# OpenScoreboard.net
KiCad netlist of a schematic drawn in EAGLE
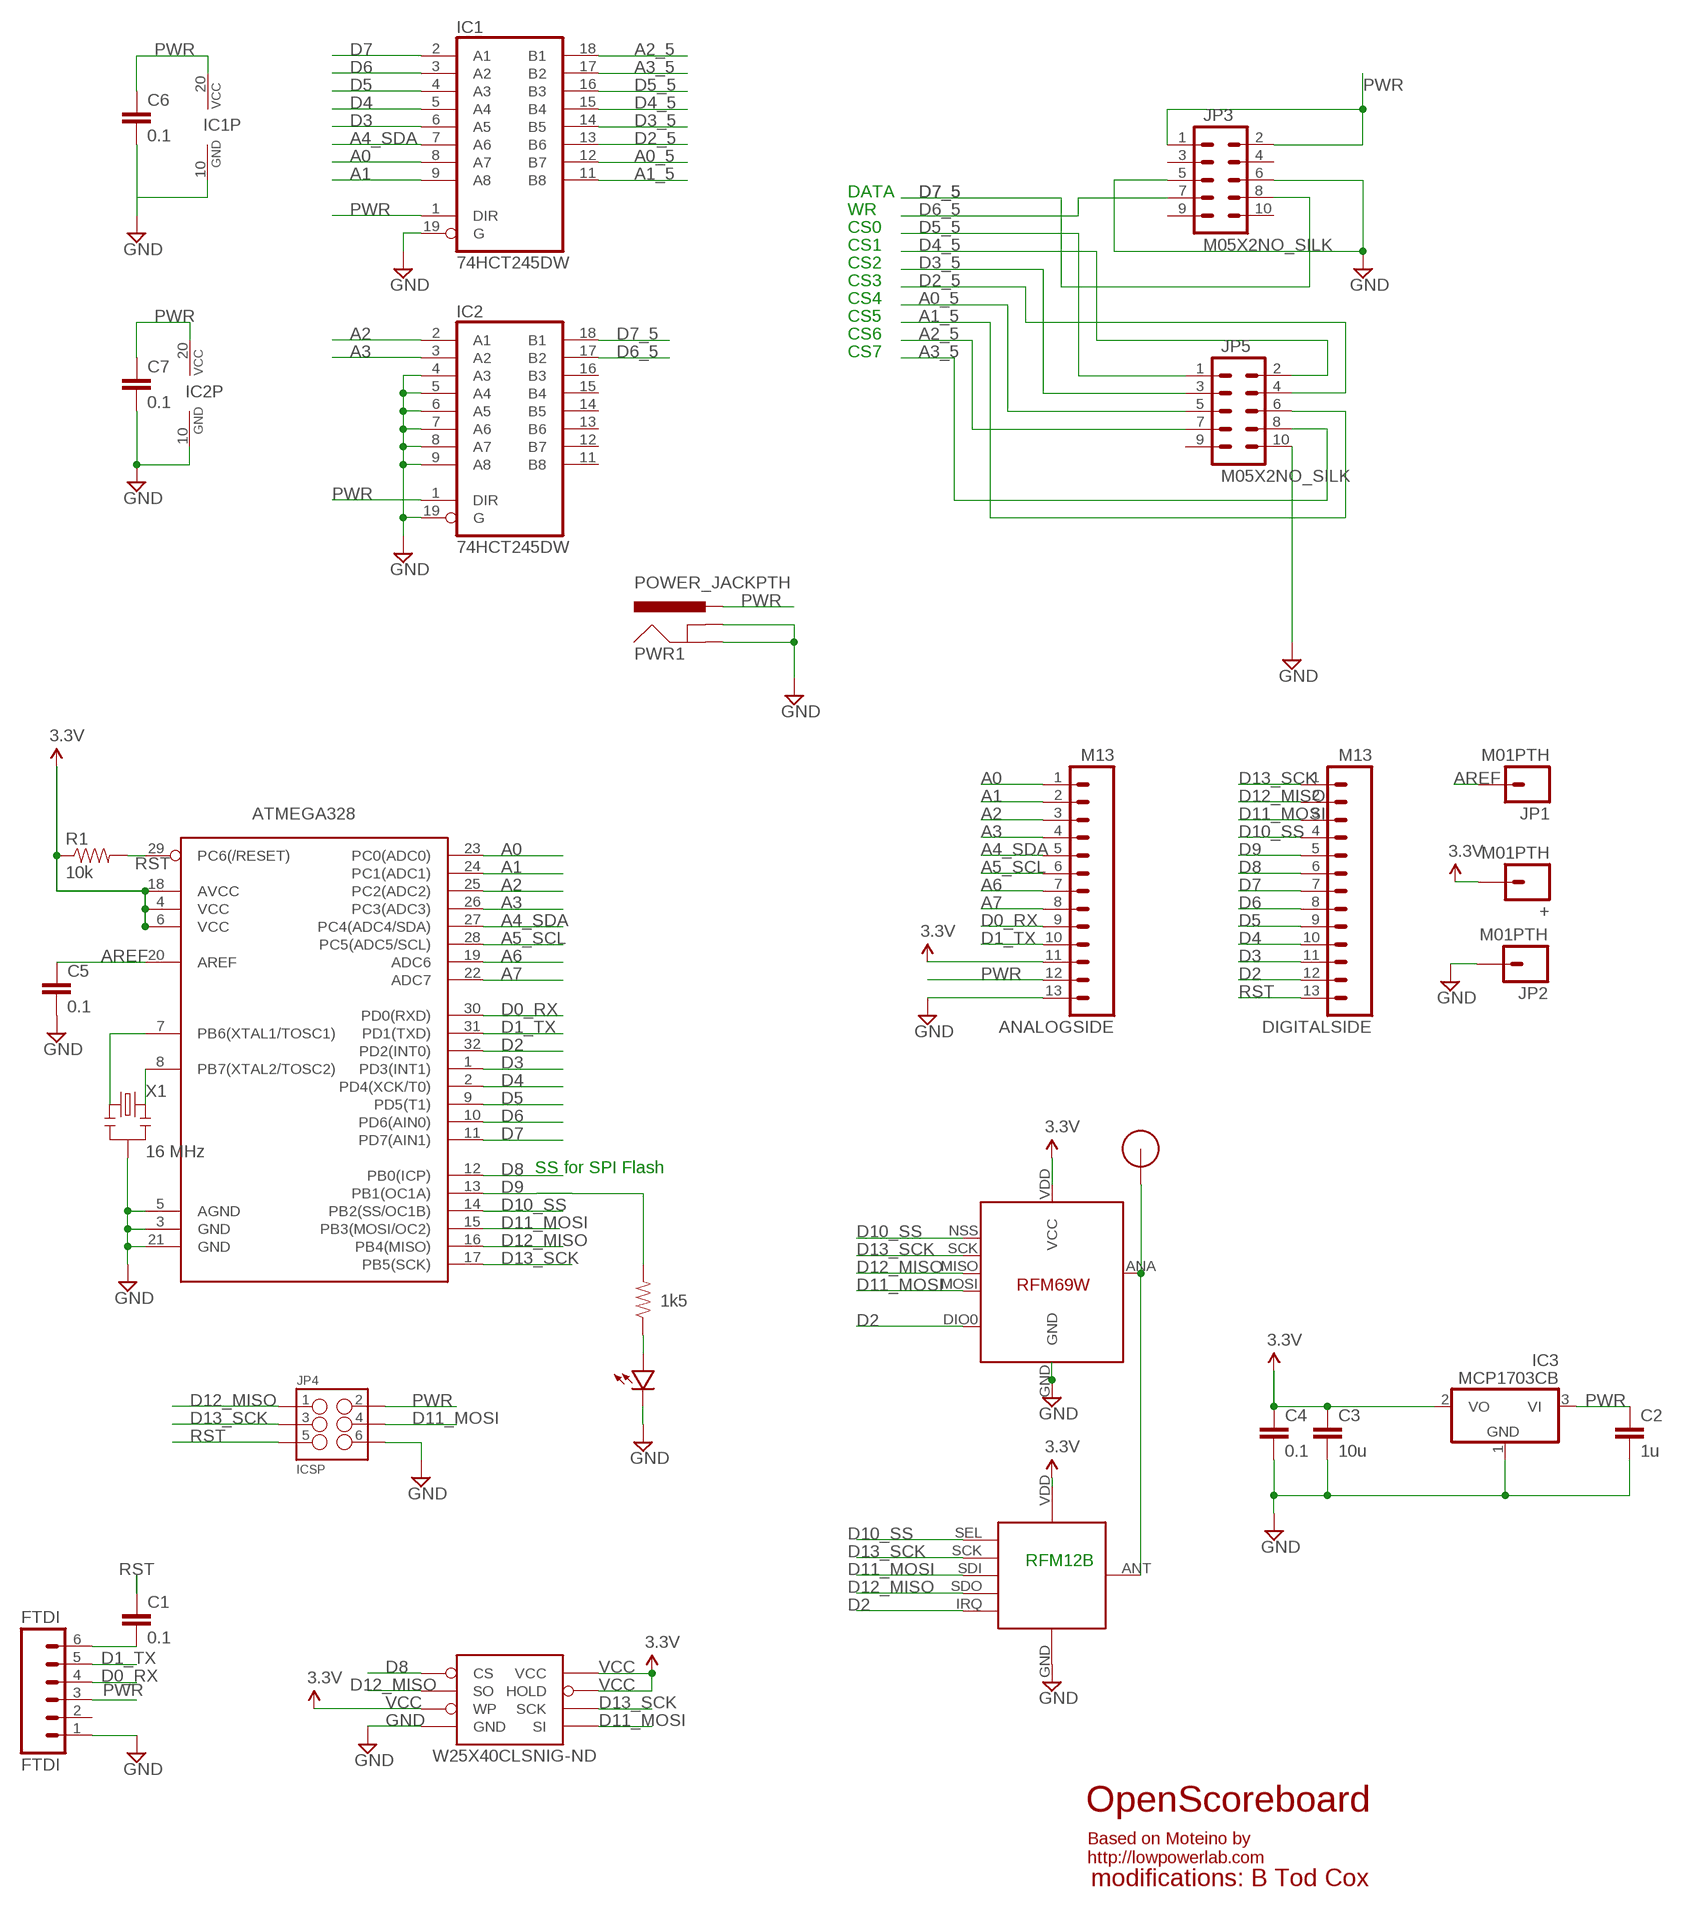
[diagram p0: schematic, sheet 1]

(export (version "E")
  (design (tool "Eeschema 10.0.6"))
  (components
    (comp (ref "+")
      (value "M01PTH")
      (footprint "eagle-import:1X01")
      (libsource (lib "eagle-import") (part "M01PTH"))
    )
    (comp (ref "ANALOGSIDE")
      (value "M13")
      (footprint "eagle-import:1X13")
      (libsource (lib "eagle-import") (part "M13"))
    )
    (comp (ref "ATMEGA328")
      (value "ATMega-328")
      (footprint "eagle-import:TQFP32-08")
      (libsource (lib "eagle-import") (part "ATMEGA168/328TQFP32"))
    )
    (comp (ref "C1")
      (value "0.1")
      (footprint "eagle-import:0603-CAP")
      (libsource (lib "eagle-import") (part "CAP0603-CAP"))
    )
    (comp (ref "C2")
      (value "1u")
      (footprint "eagle-import:0603-CAP")
      (libsource (lib "eagle-import") (part "CAP0603-CAP"))
    )
    (comp (ref "C3")
      (value "10u")
      (footprint "eagle-import:0805-CAP")
      (libsource (lib "eagle-import") (part "CAP0805-CAP"))
    )
    (comp (ref "C4")
      (value "0.1")
      (footprint "eagle-import:0603-CAP")
      (libsource (lib "eagle-import") (part "CAP0603-CAP"))
    )
    (comp (ref "C5")
      (value "0.1")
      (footprint "eagle-import:0603-CAP")
      (libsource (lib "eagle-import") (part "CAP0603-CAP"))
    )
    (comp (ref "C6")
      (value "0.1")
      (footprint "eagle-import:0603-CAP")
      (libsource (lib "eagle-import") (part "CAP0603-CAP"))
    )
    (comp (ref "C7")
      (value "0.1")
      (footprint "eagle-import:0603-CAP")
      (libsource (lib "eagle-import") (part "CAP0603-CAP"))
    )
    (comp (ref "DIGITALSIDE")
      (value "M13")
      (footprint "eagle-import:1X13")
      (libsource (lib "eagle-import") (part "M13"))
    )
    (comp (ref "FTDI")
      (value "FTDI")
      (footprint "eagle-import:1X06")
      (libsource (lib "eagle-import") (part "M06SIP"))
    )
    (comp (ref "IC1")
      (value "74HCT245DW")
      (footprint "eagle-import:SO20W")
      (libsource (lib "eagle-import") (part "74245DWHCT"))
    )
    (comp (ref "IC2")
      (value "74HCT245DW")
      (footprint "eagle-import:SO20W")
      (libsource (lib "eagle-import") (part "74245DWHCT"))
    )
    (comp (ref "IC3")
      (value "MCP1703CB")
      (footprint "eagle-import:SOT23")
      (libsource (lib "eagle-import") (part "MCP1703CB"))
    )
    (comp (ref "JP1")
      (value "M01PTH")
      (footprint "eagle-import:1X01")
      (libsource (lib "eagle-import") (part "M01PTH"))
    )
    (comp (ref "JP2")
      (value "M01PTH")
      (footprint "eagle-import:1X01")
      (libsource (lib "eagle-import") (part "M01PTH"))
    )
    (comp (ref "JP3")
      (value "M05X2NO_SILK")
      (footprint "eagle-import:2X5_NOSILK")
      (libsource (lib "eagle-import") (part "M05X2NO_SILK"))
    )
    (comp (ref "JP4")
      (value "ICSP")
      (footprint "eagle-import:2X3_POGO")
      (libsource (lib "eagle-import") (part "M03X2POGO_PINS"))
    )
    (comp (ref "JP5")
      (value "M05X2NO_SILK")
      (footprint "eagle-import:2X5_NOSILK")
      (libsource (lib "eagle-import") (part "M05X2NO_SILK"))
    )
    (comp (ref "PWR1")
      (value "POWER_JACKPTH")
      (footprint "eagle-import:POWER_JACK_PTH")
      (libsource (lib "eagle-import") (part "POWER_JACKPTH"))
    )
    (comp (ref "R1")
      (value "10k")
      (footprint "eagle-import:0603-RES")
      (libsource (lib "eagle-import") (part "RESISTOR0603-RES"))
    )
    (comp (ref "R2")
      (value "1k5")
      (footprint "eagle-import:0603-RES")
      (libsource (lib "eagle-import") (part "RESISTOR0603-RES"))
    )
    (comp (ref "RFM12B")
      (value "RFM12B_MINPADS")
      (footprint "eagle-import:RFM12B-MINPADS")
      (libsource (lib "eagle-import") (part "RFM12B_MINPADS"))
    )
    (comp (ref "U$1")
      (value "RFM12B_ANTENNA")
      (footprint "eagle-import:RFM12B-ANTENNA")
      (libsource (lib "eagle-import") (part "RFM12B_ANTENNA"))
    )
    (comp (ref "U$2")
      (value "LED0603")
      (footprint "eagle-import:0603-LED")
      (libsource (lib "eagle-import") (part "LED0603"))
    )
    (comp (ref "U$5")
      (value "RFM69")
      (footprint "eagle-import:RFM69W-MINPADS")
      (libsource (lib "eagle-import") (part "RFM69"))
    )
    (comp (ref "W25X40CLSNIG-ND")
      (value "AT25F512BWIDE_5.3MM")
      (footprint "eagle-import:SO08WIDE")
      (libsource (lib "eagle-import") (part "AT25F512BWIDE_5.3MM"))
    )
    (comp (ref "X1")
      (value "16 MHz")
      (footprint "eagle-import:RESONATOR-SMD")
      (libsource (lib "eagle-import") (part "RESONATORSMD"))
    )
  )
  (nets
    (net (code "1") (name "/A0") (class "Default")
      (node (ref "ANALOGSIDE") (pin "1") (pinfunction "1_1") (pintype "passive"))
      (node (ref "ATMEGA328") (pin "23") (pinfunction "PC0(ADC0)_23") (pintype "bidirectional"))
      (node (ref "IC1") (pin "8") (pinfunction "A7_8") (pintype "bidirectional"))
    )
    (net (code "2") (name "/A0_5") (class "Default")
      (node (ref "IC1") (pin "12") (pinfunction "B7_12") (pintype "bidirectional"))
      (node (ref "JP5") (pin "5") (pinfunction "5_5") (pintype "passive"))
    )
    (net (code "3") (name "/A1") (class "Default")
      (node (ref "ANALOGSIDE") (pin "2") (pinfunction "2_2") (pintype "passive"))
      (node (ref "ATMEGA328") (pin "24") (pinfunction "PC1(ADC1)_24") (pintype "bidirectional"))
      (node (ref "IC1") (pin "9") (pinfunction "A8_9") (pintype "bidirectional"))
    )
    (net (code "4") (name "/A1_5") (class "Default")
      (node (ref "IC1") (pin "11") (pinfunction "B8_11") (pintype "bidirectional"))
      (node (ref "JP5") (pin "6") (pinfunction "6_6") (pintype "passive"))
    )
    (net (code "5") (name "/A2") (class "Default")
      (node (ref "ANALOGSIDE") (pin "3") (pinfunction "3_3") (pintype "passive"))
      (node (ref "ATMEGA328") (pin "25") (pinfunction "PC2(ADC2)_25") (pintype "bidirectional"))
      (node (ref "IC2") (pin "2") (pinfunction "A1_2") (pintype "bidirectional"))
    )
    (net (code "6") (name "/A2_5") (class "Default")
      (node (ref "IC1") (pin "18") (pinfunction "B1_18") (pintype "bidirectional"))
      (node (ref "JP5") (pin "7") (pinfunction "7_7") (pintype "passive"))
    )
    (net (code "7") (name "/A3") (class "Default")
      (node (ref "ANALOGSIDE") (pin "4") (pinfunction "4_4") (pintype "passive"))
      (node (ref "ATMEGA328") (pin "26") (pinfunction "PC3(ADC3)_26") (pintype "bidirectional"))
      (node (ref "IC2") (pin "3") (pinfunction "A2_3") (pintype "bidirectional"))
    )
    (net (code "8") (name "/A3_5") (class "Default")
      (node (ref "IC1") (pin "17") (pinfunction "B2_17") (pintype "bidirectional"))
      (node (ref "JP5") (pin "8") (pinfunction "8_8") (pintype "passive"))
    )
    (net (code "9") (name "/A4_SDA") (class "Default")
      (node (ref "ANALOGSIDE") (pin "5") (pinfunction "5_5") (pintype "passive"))
      (node (ref "ATMEGA328") (pin "27") (pinfunction "PC4(ADC4/SDA)_27") (pintype "bidirectional"))
      (node (ref "IC1") (pin "7") (pinfunction "A6_7") (pintype "bidirectional"))
    )
    (net (code "10") (name "/A5_SCL") (class "Default")
      (node (ref "ANALOGSIDE") (pin "6") (pinfunction "6_6") (pintype "passive"))
      (node (ref "ATMEGA328") (pin "28") (pinfunction "PC5(ADC5/SCL)_28") (pintype "bidirectional"))
    )
    (net (code "11") (name "/A6") (class "Default")
      (node (ref "ANALOGSIDE") (pin "7") (pinfunction "7_7") (pintype "passive"))
      (node (ref "ATMEGA328") (pin "19") (pinfunction "ADC6_19") (pintype "bidirectional"))
    )
    (net (code "12") (name "/A7") (class "Default")
      (node (ref "ANALOGSIDE") (pin "8") (pinfunction "8_8") (pintype "passive"))
      (node (ref "ATMEGA328") (pin "22") (pinfunction "ADC7_22") (pintype "bidirectional"))
    )
    (net (code "13") (name "/AREF") (class "Default")
      (node (ref "ATMEGA328") (pin "20") (pinfunction "AREF_20") (pintype "bidirectional"))
      (node (ref "C5") (pin "1") (pinfunction "1_1") (pintype "passive"))
      (node (ref "JP1") (pin "1") (pinfunction "1_1") (pintype "passive"))
    )
    (net (code "14") (name "/D0_RX") (class "Default")
      (node (ref "ANALOGSIDE") (pin "9") (pinfunction "9_9") (pintype "passive"))
      (node (ref "ATMEGA328") (pin "30") (pinfunction "PD0(RXD)_30") (pintype "bidirectional"))
      (node (ref "FTDI") (pin "4") (pinfunction "4_4") (pintype "passive"))
    )
    (net (code "15") (name "/D1_TX") (class "Default")
      (node (ref "ANALOGSIDE") (pin "10") (pinfunction "10_10") (pintype "passive"))
      (node (ref "ATMEGA328") (pin "31") (pinfunction "PD1(TXD)_31") (pintype "bidirectional"))
      (node (ref "FTDI") (pin "5") (pinfunction "5_5") (pintype "passive"))
    )
    (net (code "16") (name "/D2") (class "Default")
      (node (ref "ATMEGA328") (pin "32") (pinfunction "PD2(INT0)_32") (pintype "bidirectional"))
      (node (ref "DIGITALSIDE") (pin "12") (pinfunction "12_12") (pintype "passive"))
      (node (ref "RFM12B") (pin "IRQ") (pinfunction "IRQ_IRQ") (pintype "bidirectional"))
      (node (ref "U$5") (pin "DIO0") (pinfunction "DIO0_DIO0") (pintype "open_collector"))
    )
    (net (code "17") (name "/D2_5") (class "Default")
      (node (ref "IC1") (pin "13") (pinfunction "B6_13") (pintype "bidirectional"))
      (node (ref "JP5") (pin "4") (pinfunction "4_4") (pintype "passive"))
    )
    (net (code "18") (name "/D3") (class "Default")
      (node (ref "ATMEGA328") (pin "1") (pinfunction "PD3(INT1)_1") (pintype "bidirectional"))
      (node (ref "DIGITALSIDE") (pin "11") (pinfunction "11_11") (pintype "passive"))
      (node (ref "IC1") (pin "6") (pinfunction "A5_6") (pintype "bidirectional"))
    )
    (net (code "19") (name "/D3_5") (class "Default")
      (node (ref "IC1") (pin "14") (pinfunction "B5_14") (pintype "bidirectional"))
      (node (ref "JP5") (pin "3") (pinfunction "3_3") (pintype "passive"))
    )
    (net (code "20") (name "/D4") (class "Default")
      (node (ref "ATMEGA328") (pin "2") (pinfunction "PD4(XCK/T0)_2") (pintype "bidirectional"))
      (node (ref "DIGITALSIDE") (pin "10") (pinfunction "10_10") (pintype "passive"))
      (node (ref "IC1") (pin "5") (pinfunction "A4_5") (pintype "bidirectional"))
    )
    (net (code "21") (name "/D4_5") (class "Default")
      (node (ref "IC1") (pin "15") (pinfunction "B4_15") (pintype "bidirectional"))
      (node (ref "JP5") (pin "2") (pinfunction "2_2") (pintype "passive"))
    )
    (net (code "22") (name "/D5") (class "Default")
      (node (ref "ATMEGA328") (pin "9") (pinfunction "PD5(T1)_9") (pintype "bidirectional"))
      (node (ref "DIGITALSIDE") (pin "9") (pinfunction "9_9") (pintype "passive"))
      (node (ref "IC1") (pin "4") (pinfunction "A3_4") (pintype "bidirectional"))
    )
    (net (code "23") (name "/D5_5") (class "Default")
      (node (ref "IC1") (pin "16") (pinfunction "B3_16") (pintype "bidirectional"))
      (node (ref "JP5") (pin "1") (pinfunction "1_1") (pintype "passive"))
    )
    (net (code "24") (name "/D6") (class "Default")
      (node (ref "ATMEGA328") (pin "10") (pinfunction "PD6(AIN0)_10") (pintype "bidirectional"))
      (node (ref "DIGITALSIDE") (pin "8") (pinfunction "8_8") (pintype "passive"))
      (node (ref "IC1") (pin "3") (pinfunction "A2_3") (pintype "bidirectional"))
    )
    (net (code "25") (name "/D6_5") (class "Default")
      (node (ref "IC2") (pin "17") (pinfunction "B2_17") (pintype "bidirectional"))
      (node (ref "JP3") (pin "7") (pinfunction "7_7") (pintype "passive"))
    )
    (net (code "26") (name "/D7") (class "Default")
      (node (ref "ATMEGA328") (pin "11") (pinfunction "PD7(AIN1)_11") (pintype "bidirectional"))
      (node (ref "DIGITALSIDE") (pin "7") (pinfunction "7_7") (pintype "passive"))
      (node (ref "IC1") (pin "2") (pinfunction "A1_2") (pintype "bidirectional"))
    )
    (net (code "27") (name "/D7_5") (class "Default")
      (node (ref "IC2") (pin "18") (pinfunction "B1_18") (pintype "bidirectional"))
      (node (ref "JP3") (pin "8") (pinfunction "8_8") (pintype "passive"))
    )
    (net (code "28") (name "/D8") (class "Default")
      (node (ref "ATMEGA328") (pin "12") (pinfunction "PB0(ICP)_12") (pintype "bidirectional"))
      (node (ref "DIGITALSIDE") (pin "6") (pinfunction "6_6") (pintype "passive"))
      (node (ref "W25X40CLSNIG-ND") (pin "1") (pinfunction "CS_1") (pintype "bidirectional"))
    )
    (net (code "29") (name "/D9") (class "Default")
      (node (ref "ATMEGA328") (pin "13") (pinfunction "PB1(OC1A)_13") (pintype "bidirectional"))
      (node (ref "DIGITALSIDE") (pin "5") (pinfunction "5_5") (pintype "passive"))
      (node (ref "R2") (pin "2") (pinfunction "2_2") (pintype "passive"))
    )
    (net (code "30") (name "/D10_SS") (class "Default")
      (node (ref "ATMEGA328") (pin "14") (pinfunction "PB2(SS/OC1B)_14") (pintype "bidirectional"))
      (node (ref "DIGITALSIDE") (pin "4") (pinfunction "4_4") (pintype "passive"))
      (node (ref "RFM12B") (pin "SEL") (pinfunction "SEL_SEL") (pintype "bidirectional"))
      (node (ref "U$5") (pin "NSS") (pinfunction "SEL_NSS") (pintype "input"))
    )
    (net (code "31") (name "/D11_MOSI") (class "Default")
      (node (ref "ATMEGA328") (pin "15") (pinfunction "PB3(MOSI/OC2)_15") (pintype "bidirectional"))
      (node (ref "DIGITALSIDE") (pin "3") (pinfunction "3_3") (pintype "passive"))
      (node (ref "JP4") (pin "P$4") (pinfunction "4_P$4") (pintype "bidirectional"))
      (node (ref "RFM12B") (pin "SDI") (pinfunction "SDI/MOSI_SDI") (pintype "bidirectional"))
      (node (ref "U$5") (pin "MOSI") (pinfunction "MOSI_MOSI") (pintype "output"))
      (node (ref "W25X40CLSNIG-ND") (pin "5") (pinfunction "SI_5") (pintype "bidirectional"))
    )
    (net (code "32") (name "/D12_MISO") (class "Default")
      (node (ref "ATMEGA328") (pin "16") (pinfunction "PB4(MISO)_16") (pintype "bidirectional"))
      (node (ref "DIGITALSIDE") (pin "2") (pinfunction "2_2") (pintype "passive"))
      (node (ref "JP4") (pin "P$1") (pinfunction "1_P$1") (pintype "bidirectional"))
      (node (ref "RFM12B") (pin "SDO") (pinfunction "SDO/MISO_SDO") (pintype "bidirectional"))
      (node (ref "U$5") (pin "MISO") (pinfunction "MISO_MISO") (pintype "input"))
      (node (ref "W25X40CLSNIG-ND") (pin "2") (pinfunction "SO_2") (pintype "bidirectional"))
    )
    (net (code "33") (name "/D13_SCK") (class "Default")
      (node (ref "ATMEGA328") (pin "17") (pinfunction "PB5(SCK)_17") (pintype "bidirectional"))
      (node (ref "DIGITALSIDE") (pin "1") (pinfunction "1_1") (pintype "passive"))
      (node (ref "JP4") (pin "P$3") (pinfunction "3_P$3") (pintype "bidirectional"))
      (node (ref "RFM12B") (pin "SCK") (pinfunction "SCK_SCK") (pintype "bidirectional"))
      (node (ref "U$5") (pin "SCK") (pinfunction "SCK_SCK") (pintype "input"))
      (node (ref "W25X40CLSNIG-ND") (pin "6") (pinfunction "SCK_6") (pintype "bidirectional"))
    )
    (net (code "34") (name "/PWR") (class "Default")
      (node (ref "ANALOGSIDE") (pin "12") (pinfunction "12_12") (pintype "passive"))
      (node (ref "C2") (pin "1") (pinfunction "1_1") (pintype "passive"))
      (node (ref "C6") (pin "1") (pinfunction "1_1") (pintype "passive"))
      (node (ref "C7") (pin "1") (pinfunction "1_1") (pintype "passive"))
      (node (ref "FTDI") (pin "3") (pinfunction "3_3") (pintype "passive"))
      (node (ref "IC1") (pin "1") (pinfunction "DIR_1") (pintype "input"))
      (node (ref "IC1") (pin "20") (pinfunction "VCC_20") (pintype "power_in"))
      (node (ref "IC2") (pin "1") (pinfunction "DIR_1") (pintype "input"))
      (node (ref "IC2") (pin "20") (pinfunction "VCC_20") (pintype "power_in"))
      (node (ref "IC3") (pin "3") (pinfunction "VI_3") (pintype "input"))
      (node (ref "JP3") (pin "1") (pinfunction "1_1") (pintype "passive"))
      (node (ref "JP3") (pin "2") (pinfunction "2_2") (pintype "passive"))
      (node (ref "JP4") (pin "P$2") (pinfunction "2_P$2") (pintype "bidirectional"))
      (node (ref "PWR1") (pin "PWR") (pinfunction "PWR_PWR") (pintype "bidirectional"))
    )
    (net (code "35") (name "/RST") (class "Default")
      (node (ref "ATMEGA328") (pin "29") (pinfunction "PC6(/RESET)_29") (pintype "bidirectional"))
      (node (ref "C1") (pin "1") (pinfunction "1_1") (pintype "passive"))
      (node (ref "DIGITALSIDE") (pin "13") (pinfunction "13_13") (pintype "passive"))
      (node (ref "JP4") (pin "P$5") (pinfunction "5_P$5") (pintype "bidirectional"))
      (node (ref "R1") (pin "2") (pinfunction "2_2") (pintype "passive"))
    )
    (net (code "36") (name "3.3V") (class "Default")
      (node (ref "+") (pin "1") (pinfunction "1_1") (pintype "passive"))
      (node (ref "ANALOGSIDE") (pin "11") (pinfunction "11_11") (pintype "passive"))
      (node (ref "ATMEGA328") (pin "18") (pinfunction "AVCC_18") (pintype "bidirectional"))
      (node (ref "ATMEGA328") (pin "4") (pinfunction "VCC_4") (pintype "bidirectional"))
      (node (ref "ATMEGA328") (pin "6") (pinfunction "VCC_6") (pintype "bidirectional"))
      (node (ref "C3") (pin "1") (pinfunction "1_1") (pintype "passive"))
      (node (ref "C4") (pin "1") (pinfunction "1_1") (pintype "passive"))
      (node (ref "IC3") (pin "2") (pinfunction "VO_2") (pintype "passive"))
      (node (ref "R1") (pin "1") (pinfunction "1_1") (pintype "passive"))
      (node (ref "RFM12B") (pin "VDD") (pinfunction "VDD_VDD") (pintype "bidirectional"))
      (node (ref "U$5") (pin "VDD") (pinfunction "VCC_VDD") (pintype "power_in"))
      (node (ref "W25X40CLSNIG-ND") (pin "3") (pinfunction "WP_3") (pintype "bidirectional"))
      (node (ref "W25X40CLSNIG-ND") (pin "7") (pinfunction "HOLD_7") (pintype "bidirectional"))
      (node (ref "W25X40CLSNIG-ND") (pin "8") (pinfunction "VCC_8") (pintype "bidirectional"))
    )
    (net (code "37") (name "GND") (class "Default")
      (node (ref "ANALOGSIDE") (pin "13") (pinfunction "13_13") (pintype "passive"))
      (node (ref "ATMEGA328") (pin "21") (pinfunction "GND_21") (pintype "bidirectional"))
      (node (ref "ATMEGA328") (pin "3") (pinfunction "GND_3") (pintype "bidirectional"))
      (node (ref "ATMEGA328") (pin "5") (pinfunction "AGND_5") (pintype "bidirectional"))
      (node (ref "C2") (pin "2") (pinfunction "2_2") (pintype "passive"))
      (node (ref "C3") (pin "2") (pinfunction "2_2") (pintype "passive"))
      (node (ref "C4") (pin "2") (pinfunction "2_2") (pintype "passive"))
      (node (ref "C5") (pin "2") (pinfunction "2_2") (pintype "passive"))
      (node (ref "C6") (pin "2") (pinfunction "2_2") (pintype "passive"))
      (node (ref "C7") (pin "2") (pinfunction "2_2") (pintype "passive"))
      (node (ref "FTDI") (pin "1") (pinfunction "1_1") (pintype "passive"))
      (node (ref "IC1") (pin "10") (pinfunction "GND_10") (pintype "power_in"))
      (node (ref "IC1") (pin "19") (pinfunction "G_19") (pintype "input"))
      (node (ref "IC2") (pin "10") (pinfunction "GND_10") (pintype "power_in"))
      (node (ref "IC2") (pin "19") (pinfunction "G_19") (pintype "input"))
      (node (ref "IC2") (pin "4") (pinfunction "A3_4") (pintype "bidirectional"))
      (node (ref "IC2") (pin "5") (pinfunction "A4_5") (pintype "bidirectional"))
      (node (ref "IC2") (pin "6") (pinfunction "A5_6") (pintype "bidirectional"))
      (node (ref "IC2") (pin "7") (pinfunction "A6_7") (pintype "bidirectional"))
      (node (ref "IC2") (pin "8") (pinfunction "A7_8") (pintype "bidirectional"))
      (node (ref "IC2") (pin "9") (pinfunction "A8_9") (pintype "bidirectional"))
      (node (ref "IC3") (pin "1") (pinfunction "GND_1") (pintype "passive"))
      (node (ref "JP2") (pin "1") (pinfunction "1_1") (pintype "passive"))
      (node (ref "JP3") (pin "5") (pinfunction "5_5") (pintype "passive"))
      (node (ref "JP3") (pin "6") (pinfunction "6_6") (pintype "passive"))
      (node (ref "JP4") (pin "P$6") (pinfunction "6_P$6") (pintype "bidirectional"))
      (node (ref "JP5") (pin "10") (pinfunction "10_10") (pintype "passive"))
      (node (ref "PWR1") (pin "GND") (pinfunction "GND_GND") (pintype "bidirectional"))
      (node (ref "PWR1") (pin "GNDBREAK") (pinfunction "GNDBREAK_GNDBREAK") (pintype "bidirectional"))
      (node (ref "RFM12B") (pin "GND") (pinfunction "GND_GND") (pintype "bidirectional"))
      (node (ref "U$2") (pin "MINUS") (pinfunction "MINUS_MINUS") (pintype "passive"))
      (node (ref "U$5") (pin "GND") (pinfunction "GND_GND") (pintype "power_in"))
      (node (ref "W25X40CLSNIG-ND") (pin "4") (pinfunction "GND_4") (pintype "bidirectional"))
      (node (ref "X1") (pin "2") (pinfunction "2_2") (pintype "passive"))
    )
    (net (code "38") (name "Net-(ATMEGA328-PB6(XTAL1{slash}TOSC1))") (class "Default")
      (node (ref "ATMEGA328") (pin "7") (pinfunction "PB6(XTAL1/TOSC1)_7") (pintype "bidirectional"))
      (node (ref "X1") (pin "1") (pinfunction "1_1") (pintype "passive"))
    )
    (net (code "39") (name "Net-(ATMEGA328-PB7(XTAL2{slash}TOSC2))") (class "Default")
      (node (ref "ATMEGA328") (pin "8") (pinfunction "PB7(XTAL2/TOSC2)_8") (pintype "bidirectional"))
      (node (ref "X1") (pin "3") (pinfunction "3_3") (pintype "passive"))
    )
    (net (code "40") (name "Net-(C1-Pad2)") (class "Default")
      (node (ref "C1") (pin "2") (pinfunction "2_2") (pintype "passive"))
      (node (ref "FTDI") (pin "6") (pinfunction "6_6") (pintype "passive"))
    )
    (net (code "41") (name "Net-(R2-Pad1)") (class "Default")
      (node (ref "R2") (pin "1") (pinfunction "1_1") (pintype "passive"))
      (node (ref "U$2") (pin "PLUS") (pinfunction "PLUS_PLUS") (pintype "passive"))
    )
    (net (code "42") (name "Net-(U$1-1)") (class "Default")
      (node (ref "RFM12B") (pin "ANT") (pinfunction "ANT_ANT") (pintype "bidirectional"))
      (node (ref "U$1") (pin "P$1") (pinfunction "1_P$1") (pintype "bidirectional"))
      (node (ref "U$5") (pin "ANA") (pinfunction "ANT_ANA") (pintype "passive"))
    )
    (net (code "43") (name "unconnected-(FTDI-Pad2)") (class "Default")
      (node (ref "FTDI") (pin "2") (pinfunction "2_2") (pintype "passive"))
    )
    (net (code "44") (name "unconnected-(IC2A-B3-Pad16)") (class "Default")
      (node (ref "IC2") (pin "16") (pinfunction "B3_16") (pintype "bidirectional"))
    )
    (net (code "45") (name "unconnected-(IC2A-B4-Pad15)") (class "Default")
      (node (ref "IC2") (pin "15") (pinfunction "B4_15") (pintype "bidirectional"))
    )
    (net (code "46") (name "unconnected-(IC2A-B5-Pad14)") (class "Default")
      (node (ref "IC2") (pin "14") (pinfunction "B5_14") (pintype "bidirectional"))
    )
    (net (code "47") (name "unconnected-(IC2A-B6-Pad13)") (class "Default")
      (node (ref "IC2") (pin "13") (pinfunction "B6_13") (pintype "bidirectional"))
    )
    (net (code "48") (name "unconnected-(IC2A-B7-Pad12)") (class "Default")
      (node (ref "IC2") (pin "12") (pinfunction "B7_12") (pintype "bidirectional"))
    )
    (net (code "49") (name "unconnected-(IC2A-B8-Pad11)") (class "Default")
      (node (ref "IC2") (pin "11") (pinfunction "B8_11") (pintype "bidirectional"))
    )
    (net (code "50") (name "unconnected-(JP3-Pad3)") (class "Default")
      (node (ref "JP3") (pin "3") (pinfunction "3_3") (pintype "passive"))
    )
    (net (code "51") (name "unconnected-(JP3-Pad4)") (class "Default")
      (node (ref "JP3") (pin "4") (pinfunction "4_4") (pintype "passive"))
    )
    (net (code "52") (name "unconnected-(JP3-Pad9)") (class "Default")
      (node (ref "JP3") (pin "9") (pinfunction "9_9") (pintype "passive"))
    )
    (net (code "53") (name "unconnected-(JP3-Pad10)") (class "Default")
      (node (ref "JP3") (pin "10") (pinfunction "10_10") (pintype "passive"))
    )
    (net (code "54") (name "unconnected-(JP5-Pad9)") (class "Default")
      (node (ref "JP5") (pin "9") (pinfunction "9_9") (pintype "passive"))
    )
  )
)
